# Power_Distro_Board_V3.net
KiCad netlist of a schematic drawn in EAGLE
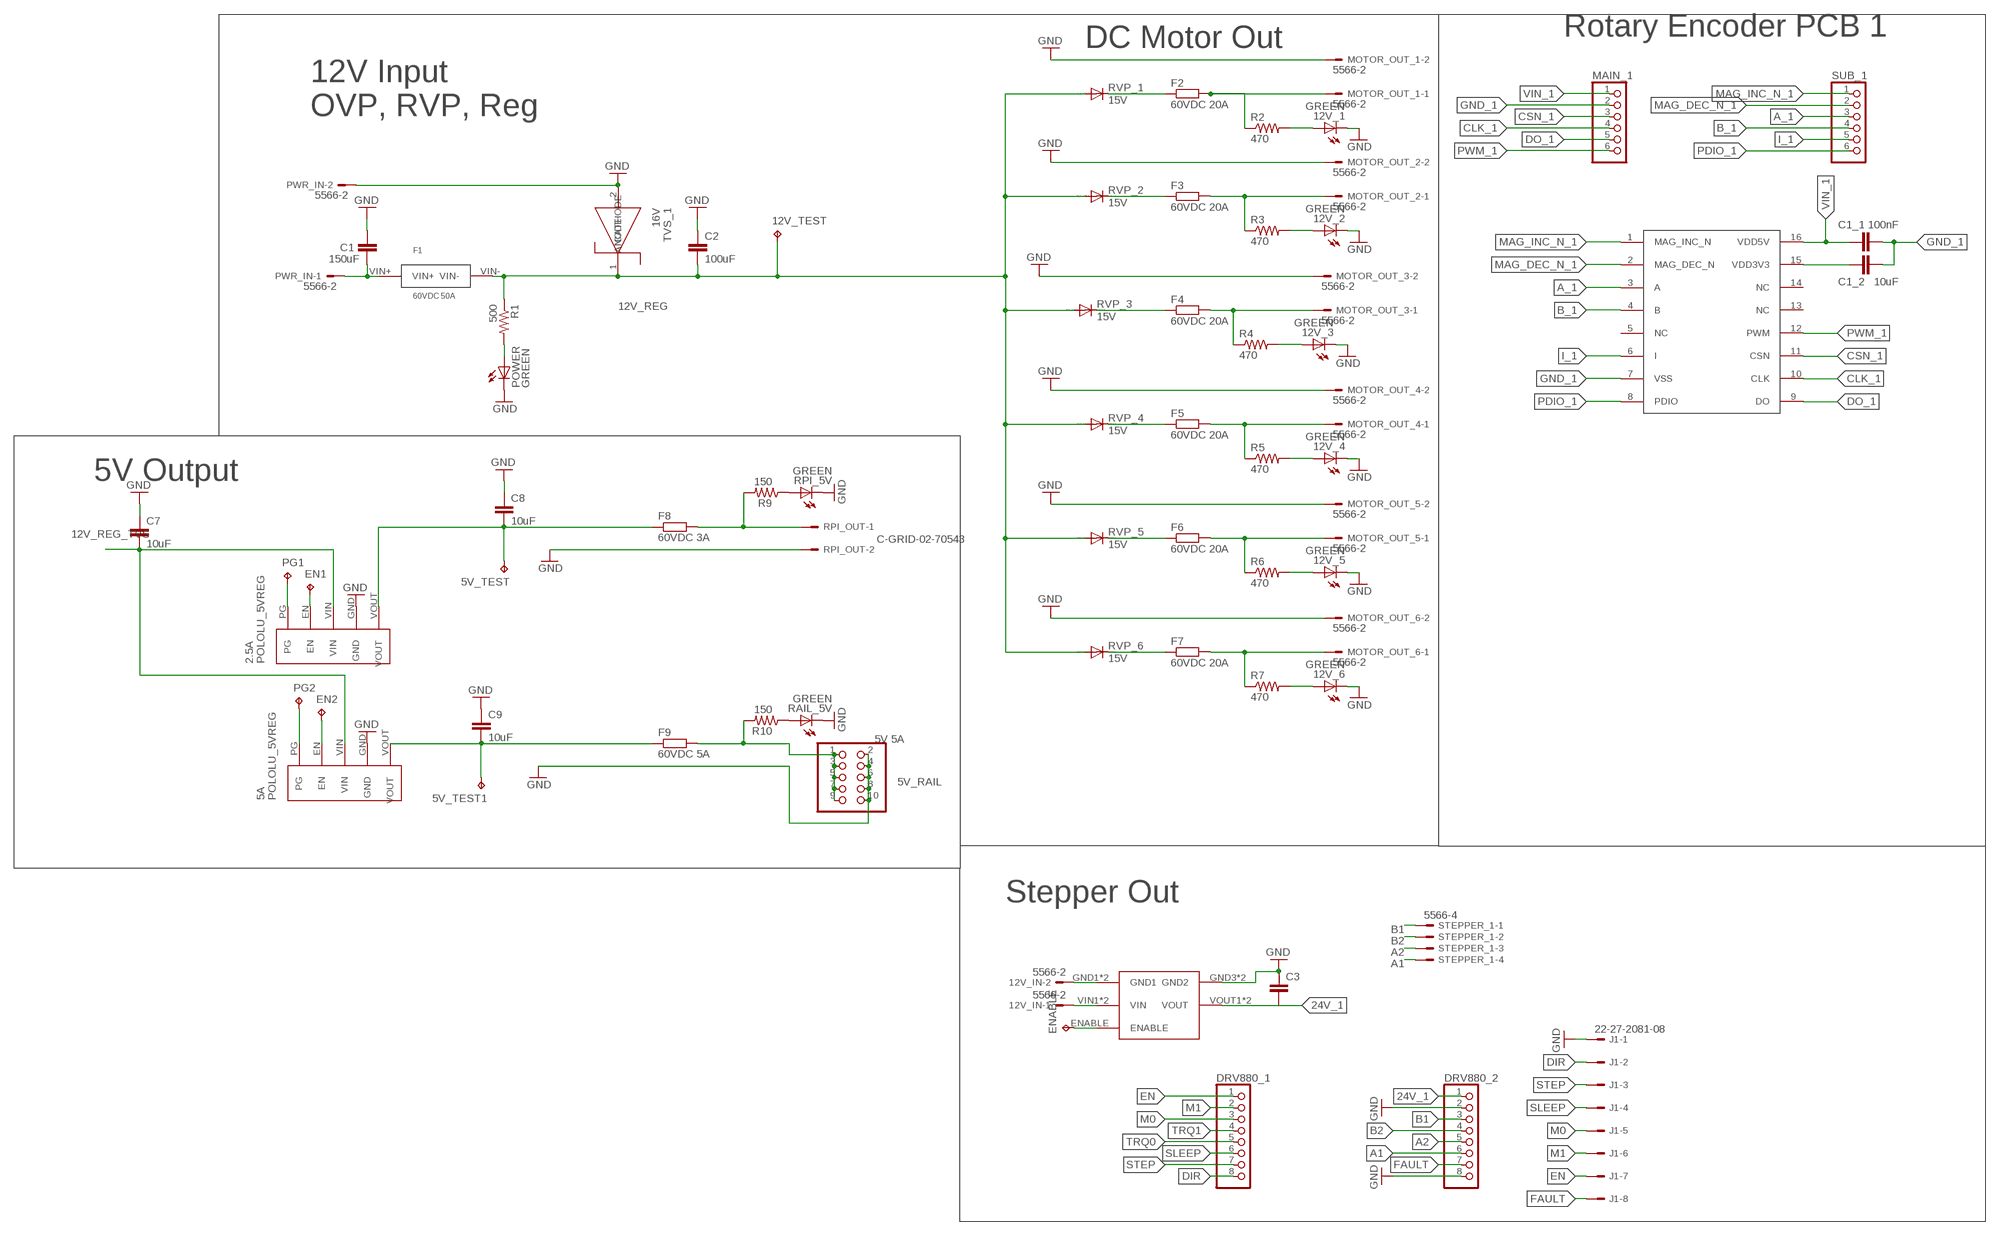
[diagram p0: schematic, sheet 1]

(export (version "E")
  (design (tool "Eeschema 10.0.6"))
  (components
    (comp (ref "2.5A")
      (value "POLOLU_5VREG")
      (footprint "eagle-import:SIP5")
      (libsource (lib "eagle-import") (part "POLOLU_5VREG"))
    )
    (comp (ref "5A")
      (value "POLOLU_5VREG")
      (footprint "eagle-import:SIP5")
      (libsource (lib "eagle-import") (part "POLOLU_5VREG"))
    )
    (comp (ref "5V_RAIL")
      (value "5V 5A")
      (footprint "eagle-import:2X05")
      (libsource (lib "eagle-import") (part "PINHD-2X5"))
    )
    (comp (ref "5V_TEST")
      (value "TPPAD1-13")
      (footprint "eagle-import:P1-13")
      (libsource (lib "eagle-import") (part "TPPAD1-13"))
    )
    (comp (ref "5V_TEST1")
      (value "TPPAD1-13")
      (footprint "eagle-import:P1-13")
      (libsource (lib "eagle-import") (part "TPPAD1-13"))
    )
    (comp (ref "12V_1")
      (value "GREEN")
      (footprint "eagle-import:SML1206")
      (libsource (lib "eagle-import") (part "LEDSML1206"))
    )
    (comp (ref "12V_2")
      (value "GREEN")
      (footprint "eagle-import:SML1206")
      (libsource (lib "eagle-import") (part "LEDSML1206"))
    )
    (comp (ref "12V_3")
      (value "GREEN")
      (footprint "eagle-import:SML1206")
      (libsource (lib "eagle-import") (part "LEDSML1206"))
    )
    (comp (ref "12V_4")
      (value "GREEN")
      (footprint "eagle-import:SML1206")
      (libsource (lib "eagle-import") (part "LEDSML1206"))
    )
    (comp (ref "12V_5")
      (value "GREEN")
      (footprint "eagle-import:SML1206")
      (libsource (lib "eagle-import") (part "LEDSML1206"))
    )
    (comp (ref "12V_6")
      (value "GREEN")
      (footprint "eagle-import:SML1206")
      (libsource (lib "eagle-import") (part "LEDSML1206"))
    )
    (comp (ref "12V_IN")
      (value "5566-2")
      (footprint "eagle-import:5566-2")
      (libsource (lib "eagle-import") (part "5566-2"))
    )
    (comp (ref "12V_TEST")
      (value "TPPAD1-13")
      (footprint "eagle-import:P1-13")
      (libsource (lib "eagle-import") (part "TPPAD1-13"))
    )
    (comp (ref "C1")
      (value "150uF")
      (footprint "eagle-import:C1206")
      (libsource (lib "eagle-import") (part "C-EUC1206"))
    )
    (comp (ref "C1_1")
      (value "100nF")
      (footprint "eagle-import:C1206")
      (libsource (lib "eagle-import") (part "C-EUC1206"))
    )
    (comp (ref "C1_2")
      (value "10uF")
      (footprint "eagle-import:C1206")
      (libsource (lib "eagle-import") (part "C-EUC1206"))
    )
    (comp (ref "C2")
      (value "100uF")
      (footprint "eagle-import:C1206")
      (libsource (lib "eagle-import") (part "C-EUC1206"))
    )
    (comp (ref "C3")
      (value "C-EUC1206")
      (footprint "eagle-import:C1206")
      (libsource (lib "eagle-import") (part "C-EUC1206"))
    )
    (comp (ref "C7")
      (value "10uF")
      (footprint "eagle-import:C1206")
      (libsource (lib "eagle-import") (part "C-EUC1206"))
    )
    (comp (ref "C8")
      (value "10uF")
      (footprint "eagle-import:C1206")
      (libsource (lib "eagle-import") (part "C-EUC1206"))
    )
    (comp (ref "C9")
      (value "10uF")
      (footprint "eagle-import:C1206")
      (libsource (lib "eagle-import") (part "C-EUC1206"))
    )
    (comp (ref "DRV880_1")
      (value "PINHD-1X8")
      (footprint "eagle-import:1X08")
      (libsource (lib "eagle-import") (part "PINHD-1X8"))
    )
    (comp (ref "DRV880_2")
      (value "PINHD-1X8")
      (footprint "eagle-import:1X08")
      (libsource (lib "eagle-import") (part "PINHD-1X8"))
    )
    (comp (ref "EN1")
      (value "TPPAD1-13")
      (footprint "eagle-import:P1-13")
      (libsource (lib "eagle-import") (part "TPPAD1-13"))
    )
    (comp (ref "EN2")
      (value "TPPAD1-13")
      (footprint "eagle-import:P1-13")
      (libsource (lib "eagle-import") (part "TPPAD1-13"))
    )
    (comp (ref "ENABLE")
      (value "TPPAD1-13")
      (footprint "eagle-import:P1-13")
      (libsource (lib "eagle-import") (part "TPPAD1-13"))
    )
    (comp (ref "ENC_1")
      (value "ENCODER_AS5045B")
      (footprint "eagle-import:SSOP16")
      (libsource (lib "eagle-import") (part "ENCODER_AS5045B"))
    )
    (comp (ref "F1")
      (value "60VDC 50A")
      (footprint "eagle-import:NANO")
      (libsource (lib "eagle-import") (part "LITTLEFUSENANO463"))
    )
    (comp (ref "F2")
      (value "60VDC 20A")
      (footprint "eagle-import:R1206W")
      (libsource (lib "eagle-import") (part "R-EU_R1206W"))
    )
    (comp (ref "F3")
      (value "60VDC 20A")
      (footprint "eagle-import:R1206W")
      (libsource (lib "eagle-import") (part "R-EU_R1206W"))
    )
    (comp (ref "F4")
      (value "60VDC 20A")
      (footprint "eagle-import:R1206W")
      (libsource (lib "eagle-import") (part "R-EU_R1206W"))
    )
    (comp (ref "F5")
      (value "60VDC 20A")
      (footprint "eagle-import:R1206W")
      (libsource (lib "eagle-import") (part "R-EU_R1206W"))
    )
    (comp (ref "F6")
      (value "60VDC 20A")
      (footprint "eagle-import:R1206W")
      (libsource (lib "eagle-import") (part "R-EU_R1206W"))
    )
    (comp (ref "F7")
      (value "60VDC 20A")
      (footprint "eagle-import:R1206W")
      (libsource (lib "eagle-import") (part "R-EU_R1206W"))
    )
    (comp (ref "F8")
      (value "60VDC 3A")
      (footprint "eagle-import:R1206W")
      (libsource (lib "eagle-import") (part "R-EU_R1206W"))
    )
    (comp (ref "F9")
      (value "60VDC 5A")
      (footprint "eagle-import:R1206W")
      (libsource (lib "eagle-import") (part "R-EU_R1206W"))
    )
    (comp (ref "J1")
      (value "22-27-2081-08")
      (footprint "eagle-import:6410-08")
      (libsource (lib "eagle-import") (part "22-?-0827-2081"))
    )
    (comp (ref "MAIN_1")
      (value "PINHD-1X6")
      (footprint "eagle-import:1X06")
      (libsource (lib "eagle-import") (part "PINHD-1X6"))
    )
    (comp (ref "MOTOR_OUT_1")
      (value "5566-2")
      (footprint "eagle-import:5566-2")
      (libsource (lib "eagle-import") (part "5566-2"))
    )
    (comp (ref "MOTOR_OUT_2")
      (value "5566-2")
      (footprint "eagle-import:5566-2")
      (libsource (lib "eagle-import") (part "5566-2"))
    )
    (comp (ref "MOTOR_OUT_3")
      (value "5566-2")
      (footprint "eagle-import:5566-2")
      (libsource (lib "eagle-import") (part "5566-2"))
    )
    (comp (ref "MOTOR_OUT_4")
      (value "5566-2")
      (footprint "eagle-import:5566-2")
      (libsource (lib "eagle-import") (part "5566-2"))
    )
    (comp (ref "MOTOR_OUT_5")
      (value "5566-2")
      (footprint "eagle-import:5566-2")
      (libsource (lib "eagle-import") (part "5566-2"))
    )
    (comp (ref "MOTOR_OUT_6")
      (value "5566-2")
      (footprint "eagle-import:5566-2")
      (libsource (lib "eagle-import") (part "5566-2"))
    )
    (comp (ref "PG1")
      (value "TPPAD1-13")
      (footprint "eagle-import:P1-13")
      (libsource (lib "eagle-import") (part "TPPAD1-13"))
    )
    (comp (ref "PG2")
      (value "TPPAD1-13")
      (footprint "eagle-import:P1-13")
      (libsource (lib "eagle-import") (part "TPPAD1-13"))
    )
    (comp (ref "POWER")
      (value "GREEN")
      (footprint "eagle-import:SML1206")
      (libsource (lib "eagle-import") (part "LEDSML1206"))
    )
    (comp (ref "PWR_IN")
      (value "5566-2")
      (footprint "eagle-import:5566-2")
      (libsource (lib "eagle-import") (part "5566-2"))
    )
    (comp (ref "R1")
      (value "500")
      (footprint "eagle-import:R1206")
      (libsource (lib "eagle-import") (part "R-US_R1206"))
    )
    (comp (ref "R2")
      (value "470")
      (footprint "eagle-import:R1206")
      (libsource (lib "eagle-import") (part "R-US_R1206"))
    )
    (comp (ref "R3")
      (value "470")
      (footprint "eagle-import:R1206")
      (libsource (lib "eagle-import") (part "R-US_R1206"))
    )
    (comp (ref "R4")
      (value "470")
      (footprint "eagle-import:R1206")
      (libsource (lib "eagle-import") (part "R-US_R1206"))
    )
    (comp (ref "R5")
      (value "470")
      (footprint "eagle-import:R1206")
      (libsource (lib "eagle-import") (part "R-US_R1206"))
    )
    (comp (ref "R6")
      (value "470")
      (footprint "eagle-import:R1206")
      (libsource (lib "eagle-import") (part "R-US_R1206"))
    )
    (comp (ref "R7")
      (value "470")
      (footprint "eagle-import:R1206")
      (libsource (lib "eagle-import") (part "R-US_R1206"))
    )
    (comp (ref "R9")
      (value "150")
      (footprint "eagle-import:R1206")
      (libsource (lib "eagle-import") (part "R-US_R1206"))
    )
    (comp (ref "R10")
      (value "150")
      (footprint "eagle-import:R1206")
      (libsource (lib "eagle-import") (part "R-US_R1206"))
    )
    (comp (ref "RAIL_5V")
      (value "GREEN")
      (footprint "eagle-import:SML1206")
      (libsource (lib "eagle-import") (part "LEDSML1206"))
    )
    (comp (ref "RPI_5V")
      (value "GREEN")
      (footprint "eagle-import:SML1206")
      (libsource (lib "eagle-import") (part "LEDSML1206"))
    )
    (comp (ref "RPI_OUT")
      (value "C-GRID-02-70543")
      (footprint "eagle-import:70543-02")
      (libsource (lib "eagle-import") (part "C-GRID-02-70543"))
    )
    (comp (ref "RVP_1")
      (value "15V")
      (footprint "eagle-import:TO220ACS")
      (libsource (lib "eagle-import") (part "BYT08P"))
    )
    (comp (ref "RVP_2")
      (value "15V")
      (footprint "eagle-import:TO220ACS")
      (libsource (lib "eagle-import") (part "BYT08P"))
    )
    (comp (ref "RVP_3")
      (value "15V")
      (footprint "eagle-import:TO220ACS")
      (libsource (lib "eagle-import") (part "BYT08P"))
    )
    (comp (ref "RVP_4")
      (value "15V")
      (footprint "eagle-import:TO220ACS")
      (libsource (lib "eagle-import") (part "BYT08P"))
    )
    (comp (ref "RVP_5")
      (value "15V")
      (footprint "eagle-import:TO220ACS")
      (libsource (lib "eagle-import") (part "BYT08P"))
    )
    (comp (ref "RVP_6")
      (value "15V")
      (footprint "eagle-import:TO220ACS")
      (libsource (lib "eagle-import") (part "BYT08P"))
    )
    (comp (ref "STEPPER_1")
      (value "5566-4")
      (footprint "eagle-import:5566-4")
      (libsource (lib "eagle-import") (part "5566-4"))
    )
    (comp (ref "SUB_1")
      (value "PINHD-1X6")
      (footprint "eagle-import:1X06")
      (libsource (lib "eagle-import") (part "PINHD-1X6"))
    )
    (comp (ref "TVS_1")
      (value "16V")
      (footprint "eagle-import:DO-214AC")
      (libsource (lib "eagle-import") (part "SMAJ26A_TVSSMA"))
    )
    (comp (ref "U$1")
      (value "POLOLU_24VSTEPUP")
      (footprint "eagle-import:2X4PIN_REG")
      (libsource (lib "eagle-import") (part "POLOLU_24VSTEPUP"))
    )
  )
  (nets
    (net (code "1") (name "/12V_REG") (class "Default")
      (node (ref "12V_TEST") (pin "TP") (pinfunction "TP_TP") (pintype "input"))
      (node (ref "C2") (pin "2") (pinfunction "2_2") (pintype "passive"))
      (node (ref "F1") (pin "VIN-") (pinfunction "VIN-_VIN-") (pintype "bidirectional"))
      (node (ref "R1") (pin "1") (pinfunction "1_1") (pintype "passive"))
      (node (ref "RVP_1") (pin "A") (pinfunction "A_A") (pintype "passive"))
      (node (ref "RVP_2") (pin "A") (pinfunction "A_A") (pintype "passive"))
      (node (ref "RVP_3") (pin "A") (pinfunction "A_A") (pintype "passive"))
      (node (ref "RVP_4") (pin "A") (pinfunction "A_A") (pintype "passive"))
      (node (ref "RVP_5") (pin "A") (pinfunction "A_A") (pintype "passive"))
      (node (ref "RVP_6") (pin "A") (pinfunction "A_A") (pintype "passive"))
      (node (ref "TVS_1") (pin "1") (pinfunction "CATHODE_1") (pintype "bidirectional"))
    )
    (net (code "2") (name "/12V_REG_TVS") (class "Default")
      (node (ref "2.5A") (pin "VIN") (pinfunction "VIN_VIN") (pintype "bidirectional"))
      (node (ref "5A") (pin "VIN") (pinfunction "VIN_VIN") (pintype "bidirectional"))
      (node (ref "C7") (pin "2") (pinfunction "2_2") (pintype "passive"))
    )
    (net (code "3") (name "24V_1") (class "Default")
      (node (ref "DRV880_2") (pin "1") (pinfunction "1_1") (pintype "passive"))
      (node (ref "U$1") (pin "VOUT1") (pinfunction "VOUT_VOUT1") (pintype "bidirectional"))
      (node (ref "U$1") (pin "VOUT2") (pinfunction "VOUT_VOUT2") (pintype "bidirectional"))
    )
    (net (code "4") (name "A1") (class "Default")
      (node (ref "DRV880_2") (pin "6") (pinfunction "6_6") (pintype "passive"))
      (node (ref "STEPPER_1") (pin "4") (pinfunction "S_4") (pintype "passive"))
    )
    (net (code "5") (name "A2") (class "Default")
      (node (ref "DRV880_2") (pin "5") (pinfunction "5_5") (pintype "passive"))
      (node (ref "STEPPER_1") (pin "3") (pinfunction "S_3") (pintype "passive"))
    )
    (net (code "6") (name "A_1") (class "Default")
      (node (ref "ENC_1") (pin "3") (pinfunction "A_3") (pintype "bidirectional"))
      (node (ref "SUB_1") (pin "3") (pinfunction "3_3") (pintype "passive"))
    )
    (net (code "7") (name "B1") (class "Default")
      (node (ref "DRV880_2") (pin "3") (pinfunction "3_3") (pintype "passive"))
      (node (ref "STEPPER_1") (pin "1") (pinfunction "S_1") (pintype "passive"))
    )
    (net (code "8") (name "B2") (class "Default")
      (node (ref "DRV880_2") (pin "4") (pinfunction "4_4") (pintype "passive"))
      (node (ref "STEPPER_1") (pin "2") (pinfunction "S_2") (pintype "passive"))
    )
    (net (code "9") (name "B_1") (class "Default")
      (node (ref "ENC_1") (pin "4") (pinfunction "B_4") (pintype "bidirectional"))
      (node (ref "SUB_1") (pin "4") (pinfunction "4_4") (pintype "passive"))
    )
    (net (code "10") (name "CLK_1") (class "Default")
      (node (ref "ENC_1") (pin "10") (pinfunction "CLK_10") (pintype "bidirectional"))
      (node (ref "MAIN_1") (pin "4") (pinfunction "4_4") (pintype "passive"))
    )
    (net (code "11") (name "CSN_1") (class "Default")
      (node (ref "ENC_1") (pin "11") (pinfunction "CSN_11") (pintype "bidirectional"))
      (node (ref "MAIN_1") (pin "3") (pinfunction "3_3") (pintype "passive"))
    )
    (net (code "12") (name "DIR") (class "Default")
      (node (ref "DRV880_1") (pin "8") (pinfunction "8_8") (pintype "passive"))
      (node (ref "J1") (pin "2") (pinfunction "S_2") (pintype "passive"))
    )
    (net (code "13") (name "DO_1") (class "Default")
      (node (ref "ENC_1") (pin "9") (pinfunction "DO_9") (pintype "bidirectional"))
      (node (ref "MAIN_1") (pin "5") (pinfunction "5_5") (pintype "passive"))
    )
    (net (code "14") (name "EN") (class "Default")
      (node (ref "DRV880_1") (pin "1") (pinfunction "1_1") (pintype "passive"))
      (node (ref "J1") (pin "7") (pinfunction "S_7") (pintype "passive"))
    )
    (net (code "15") (name "FAULT") (class "Default")
      (node (ref "DRV880_2") (pin "7") (pinfunction "7_7") (pintype "passive"))
      (node (ref "J1") (pin "8") (pinfunction "S_8") (pintype "passive"))
    )
    (net (code "16") (name "GND") (class "Default")
      (node (ref "12V_1") (pin "C") (pinfunction "C_C") (pintype "passive"))
      (node (ref "12V_2") (pin "C") (pinfunction "C_C") (pintype "passive"))
      (node (ref "12V_3") (pin "C") (pinfunction "C_C") (pintype "passive"))
      (node (ref "12V_4") (pin "C") (pinfunction "C_C") (pintype "passive"))
      (node (ref "12V_5") (pin "C") (pinfunction "C_C") (pintype "passive"))
      (node (ref "12V_6") (pin "C") (pinfunction "C_C") (pintype "passive"))
      (node (ref "2.5A") (pin "GND") (pinfunction "GND_GND") (pintype "bidirectional"))
      (node (ref "5A") (pin "GND") (pinfunction "GND_GND") (pintype "bidirectional"))
      (node (ref "5V_RAIL") (pin "10") (pinfunction "10_10") (pintype "passive"))
      (node (ref "5V_RAIL") (pin "2") (pinfunction "2_2") (pintype "passive"))
      (node (ref "5V_RAIL") (pin "4") (pinfunction "4_4") (pintype "passive"))
      (node (ref "5V_RAIL") (pin "6") (pinfunction "6_6") (pintype "passive"))
      (node (ref "5V_RAIL") (pin "8") (pinfunction "8_8") (pintype "passive"))
      (node (ref "C1") (pin "1") (pinfunction "1_1") (pintype "passive"))
      (node (ref "C2") (pin "1") (pinfunction "1_1") (pintype "passive"))
      (node (ref "C3") (pin "1") (pinfunction "1_1") (pintype "passive"))
      (node (ref "C7") (pin "1") (pinfunction "1_1") (pintype "passive"))
      (node (ref "C8") (pin "1") (pinfunction "1_1") (pintype "passive"))
      (node (ref "C9") (pin "1") (pinfunction "1_1") (pintype "passive"))
      (node (ref "DRV880_2") (pin "2") (pinfunction "2_2") (pintype "passive"))
      (node (ref "DRV880_2") (pin "8") (pinfunction "8_8") (pintype "passive"))
      (node (ref "J1") (pin "1") (pinfunction "S_1") (pintype "passive"))
      (node (ref "MOTOR_OUT_1") (pin "2") (pinfunction "S_2") (pintype "passive"))
      (node (ref "MOTOR_OUT_2") (pin "2") (pinfunction "S_2") (pintype "passive"))
      (node (ref "MOTOR_OUT_3") (pin "2") (pinfunction "S_2") (pintype "passive"))
      (node (ref "MOTOR_OUT_4") (pin "2") (pinfunction "S_2") (pintype "passive"))
      (node (ref "MOTOR_OUT_5") (pin "2") (pinfunction "S_2") (pintype "passive"))
      (node (ref "MOTOR_OUT_6") (pin "2") (pinfunction "S_2") (pintype "passive"))
      (node (ref "POWER") (pin "C") (pinfunction "C_C") (pintype "passive"))
      (node (ref "PWR_IN") (pin "2") (pinfunction "S_2") (pintype "passive"))
      (node (ref "RAIL_5V") (pin "C") (pinfunction "C_C") (pintype "passive"))
      (node (ref "RPI_5V") (pin "C") (pinfunction "C_C") (pintype "passive"))
      (node (ref "RPI_OUT") (pin "2") (pinfunction "S_2") (pintype "passive"))
      (node (ref "TVS_1") (pin "2") (pinfunction "ANODE_2") (pintype "bidirectional"))
      (node (ref "U$1") (pin "GND3") (pinfunction "GND2_GND3") (pintype "bidirectional"))
      (node (ref "U$1") (pin "GND4") (pinfunction "GND2_GND4") (pintype "bidirectional"))
    )
    (net (code "17") (name "GND_1") (class "Default")
      (node (ref "C1_1") (pin "2") (pinfunction "2_2") (pintype "passive"))
      (node (ref "C1_2") (pin "2") (pinfunction "2_2") (pintype "passive"))
      (node (ref "ENC_1") (pin "7") (pinfunction "VSS_7") (pintype "bidirectional"))
      (node (ref "MAIN_1") (pin "2") (pinfunction "2_2") (pintype "passive"))
    )
    (net (code "18") (name "I_1") (class "Default")
      (node (ref "ENC_1") (pin "6") (pinfunction "I_6") (pintype "bidirectional"))
      (node (ref "SUB_1") (pin "5") (pinfunction "5_5") (pintype "passive"))
    )
    (net (code "19") (name "M0") (class "Default")
      (node (ref "DRV880_1") (pin "3") (pinfunction "3_3") (pintype "passive"))
      (node (ref "J1") (pin "5") (pinfunction "S_5") (pintype "passive"))
    )
    (net (code "20") (name "M1") (class "Default")
      (node (ref "DRV880_1") (pin "2") (pinfunction "2_2") (pintype "passive"))
      (node (ref "J1") (pin "6") (pinfunction "S_6") (pintype "passive"))
    )
    (net (code "21") (name "MAG_DEC_N_1") (class "Default")
      (node (ref "ENC_1") (pin "2") (pinfunction "MAG_DEC_N_2") (pintype "bidirectional"))
      (node (ref "SUB_1") (pin "2") (pinfunction "2_2") (pintype "passive"))
    )
    (net (code "22") (name "MAG_INC_N_1") (class "Default")
      (node (ref "ENC_1") (pin "1") (pinfunction "MAG_INC_N_1") (pintype "bidirectional"))
      (node (ref "SUB_1") (pin "1") (pinfunction "1_1") (pintype "passive"))
    )
    (net (code "23") (name "Net-(2.5A-PadEN)") (class "Default")
      (node (ref "2.5A") (pin "EN") (pinfunction "EN_EN") (pintype "bidirectional"))
      (node (ref "EN1") (pin "TP") (pinfunction "TP_TP") (pintype "input"))
    )
    (net (code "24") (name "Net-(2.5A-PadPG)") (class "Default")
      (node (ref "2.5A") (pin "PG") (pinfunction "PG_PG") (pintype "bidirectional"))
      (node (ref "PG1") (pin "TP") (pinfunction "TP_TP") (pintype "input"))
    )
    (net (code "25") (name "Net-(2.5A-PadVOUT)") (class "Default")
      (node (ref "2.5A") (pin "VOUT") (pinfunction "VOUT_VOUT") (pintype "bidirectional"))
      (node (ref "5V_TEST") (pin "TP") (pinfunction "TP_TP") (pintype "input"))
      (node (ref "C8") (pin "2") (pinfunction "2_2") (pintype "passive"))
      (node (ref "F8") (pin "1") (pinfunction "1_1") (pintype "passive"))
    )
    (net (code "26") (name "Net-(5A-PadEN)") (class "Default")
      (node (ref "5A") (pin "EN") (pinfunction "EN_EN") (pintype "bidirectional"))
      (node (ref "EN2") (pin "TP") (pinfunction "TP_TP") (pintype "input"))
    )
    (net (code "27") (name "Net-(5A-PadPG)") (class "Default")
      (node (ref "5A") (pin "PG") (pinfunction "PG_PG") (pintype "bidirectional"))
      (node (ref "PG2") (pin "TP") (pinfunction "TP_TP") (pintype "input"))
    )
    (net (code "28") (name "Net-(5A-PadVOUT)") (class "Default")
      (node (ref "5A") (pin "VOUT") (pinfunction "VOUT_VOUT") (pintype "bidirectional"))
      (node (ref "5V_TEST1") (pin "TP") (pinfunction "TP_TP") (pintype "input"))
      (node (ref "C9") (pin "2") (pinfunction "2_2") (pintype "passive"))
      (node (ref "F9") (pin "1") (pinfunction "1_1") (pintype "passive"))
    )
    (net (code "29") (name "Net-(5V_RAIL-Pad1)") (class "Default")
      (node (ref "5V_RAIL") (pin "1") (pinfunction "1_1") (pintype "passive"))
      (node (ref "5V_RAIL") (pin "3") (pinfunction "3_3") (pintype "passive"))
      (node (ref "5V_RAIL") (pin "5") (pinfunction "5_5") (pintype "passive"))
      (node (ref "5V_RAIL") (pin "7") (pinfunction "7_7") (pintype "passive"))
      (node (ref "5V_RAIL") (pin "9") (pinfunction "9_9") (pintype "passive"))
      (node (ref "F9") (pin "2") (pinfunction "2_2") (pintype "passive"))
      (node (ref "R10") (pin "2") (pinfunction "2_2") (pintype "passive"))
    )
    (net (code "30") (name "Net-(12V_1-PadA)") (class "Default")
      (node (ref "12V_1") (pin "A") (pinfunction "A_A") (pintype "passive"))
      (node (ref "R2") (pin "2") (pinfunction "2_2") (pintype "passive"))
    )
    (net (code "31") (name "Net-(12V_2-PadA)") (class "Default")
      (node (ref "12V_2") (pin "A") (pinfunction "A_A") (pintype "passive"))
      (node (ref "R3") (pin "2") (pinfunction "2_2") (pintype "passive"))
    )
    (net (code "32") (name "Net-(12V_3-PadA)") (class "Default")
      (node (ref "12V_3") (pin "A") (pinfunction "A_A") (pintype "passive"))
      (node (ref "R4") (pin "2") (pinfunction "2_2") (pintype "passive"))
    )
    (net (code "33") (name "Net-(12V_4-PadA)") (class "Default")
      (node (ref "12V_4") (pin "A") (pinfunction "A_A") (pintype "passive"))
      (node (ref "R5") (pin "2") (pinfunction "2_2") (pintype "passive"))
    )
    (net (code "34") (name "Net-(12V_5-PadA)") (class "Default")
      (node (ref "12V_5") (pin "A") (pinfunction "A_A") (pintype "passive"))
      (node (ref "R6") (pin "2") (pinfunction "2_2") (pintype "passive"))
    )
    (net (code "35") (name "Net-(12V_6-PadA)") (class "Default")
      (node (ref "12V_6") (pin "A") (pinfunction "A_A") (pintype "passive"))
      (node (ref "R7") (pin "2") (pinfunction "2_2") (pintype "passive"))
    )
    (net (code "36") (name "Net-(12V_INA-S)") (class "Default")
      (node (ref "12V_IN") (pin "1") (pinfunction "S_1") (pintype "passive"))
      (node (ref "U$1") (pin "VIN1") (pinfunction "VIN_VIN1") (pintype "bidirectional"))
      (node (ref "U$1") (pin "VIN2") (pinfunction "VIN_VIN2") (pintype "bidirectional"))
    )
    (net (code "37") (name "Net-(12V_INB-S)") (class "Default")
      (node (ref "12V_IN") (pin "2") (pinfunction "S_2") (pintype "passive"))
      (node (ref "U$1") (pin "GND1") (pinfunction "GND1_GND1") (pintype "bidirectional"))
      (node (ref "U$1") (pin "GND2") (pinfunction "GND1_GND2") (pintype "bidirectional"))
    )
    (net (code "38") (name "Net-(ENABLE-PadTP)") (class "Default")
      (node (ref "ENABLE") (pin "TP") (pinfunction "TP_TP") (pintype "input"))
      (node (ref "U$1") (pin "ENABLE") (pinfunction "ENABLE_ENABLE") (pintype "bidirectional"))
    )
    (net (code "39") (name "Net-(ENC_1-VDD3V3)") (class "Default")
      (node (ref "C1_2") (pin "1") (pinfunction "1_1") (pintype "passive"))
      (node (ref "ENC_1") (pin "15") (pinfunction "VDD3V3_15") (pintype "bidirectional"))
    )
    (net (code "40") (name "Net-(F2-Pad1)") (class "Default")
      (node (ref "F2") (pin "1") (pinfunction "1_1") (pintype "passive"))
      (node (ref "RVP_1") (pin "C") (pinfunction "C_C") (pintype "passive"))
    )
    (net (code "41") (name "Net-(F3-Pad1)") (class "Default")
      (node (ref "F3") (pin "1") (pinfunction "1_1") (pintype "passive"))
      (node (ref "RVP_2") (pin "C") (pinfunction "C_C") (pintype "passive"))
    )
    (net (code "42") (name "Net-(F4-Pad1)") (class "Default")
      (node (ref "F4") (pin "1") (pinfunction "1_1") (pintype "passive"))
      (node (ref "RVP_3") (pin "C") (pinfunction "C_C") (pintype "passive"))
    )
    (net (code "43") (name "Net-(F5-Pad1)") (class "Default")
      (node (ref "F5") (pin "1") (pinfunction "1_1") (pintype "passive"))
      (node (ref "RVP_4") (pin "C") (pinfunction "C_C") (pintype "passive"))
    )
    (net (code "44") (name "Net-(F6-Pad1)") (class "Default")
      (node (ref "F6") (pin "1") (pinfunction "1_1") (pintype "passive"))
      (node (ref "RVP_5") (pin "C") (pinfunction "C_C") (pintype "passive"))
    )
    (net (code "45") (name "Net-(F7-Pad1)") (class "Default")
      (node (ref "F7") (pin "1") (pinfunction "1_1") (pintype "passive"))
      (node (ref "RVP_6") (pin "C") (pinfunction "C_C") (pintype "passive"))
    )
    (net (code "46") (name "Net-(MOTOR_OUT_1A-S)") (class "Default")
      (node (ref "F2") (pin "2") (pinfunction "2_2") (pintype "passive"))
      (node (ref "MOTOR_OUT_1") (pin "1") (pinfunction "S_1") (pintype "passive"))
      (node (ref "R2") (pin "1") (pinfunction "1_1") (pintype "passive"))
    )
    (net (code "47") (name "Net-(MOTOR_OUT_2A-S)") (class "Default")
      (node (ref "F3") (pin "2") (pinfunction "2_2") (pintype "passive"))
      (node (ref "MOTOR_OUT_2") (pin "1") (pinfunction "S_1") (pintype "passive"))
      (node (ref "R3") (pin "1") (pinfunction "1_1") (pintype "passive"))
    )
    (net (code "48") (name "Net-(MOTOR_OUT_3A-S)") (class "Default")
      (node (ref "F4") (pin "2") (pinfunction "2_2") (pintype "passive"))
      (node (ref "MOTOR_OUT_3") (pin "1") (pinfunction "S_1") (pintype "passive"))
      (node (ref "R4") (pin "1") (pinfunction "1_1") (pintype "passive"))
    )
    (net (code "49") (name "Net-(MOTOR_OUT_4A-S)") (class "Default")
      (node (ref "F5") (pin "2") (pinfunction "2_2") (pintype "passive"))
      (node (ref "MOTOR_OUT_4") (pin "1") (pinfunction "S_1") (pintype "passive"))
      (node (ref "R5") (pin "1") (pinfunction "1_1") (pintype "passive"))
    )
    (net (code "50") (name "Net-(MOTOR_OUT_5A-S)") (class "Default")
      (node (ref "F6") (pin "2") (pinfunction "2_2") (pintype "passive"))
      (node (ref "MOTOR_OUT_5") (pin "1") (pinfunction "S_1") (pintype "passive"))
      (node (ref "R6") (pin "1") (pinfunction "1_1") (pintype "passive"))
    )
    (net (code "51") (name "Net-(MOTOR_OUT_6A-S)") (class "Default")
      (node (ref "F7") (pin "2") (pinfunction "2_2") (pintype "passive"))
      (node (ref "MOTOR_OUT_6") (pin "1") (pinfunction "S_1") (pintype "passive"))
      (node (ref "R7") (pin "1") (pinfunction "1_1") (pintype "passive"))
    )
    (net (code "52") (name "Net-(POWER-PadA)") (class "Default")
      (node (ref "POWER") (pin "A") (pinfunction "A_A") (pintype "passive"))
      (node (ref "R1") (pin "2") (pinfunction "2_2") (pintype "passive"))
    )
    (net (code "53") (name "Net-(PWR_INA-S)") (class "Default")
      (node (ref "C1") (pin "2") (pinfunction "2_2") (pintype "passive"))
      (node (ref "F1") (pin "VIN+") (pinfunction "VIN+_VIN+") (pintype "bidirectional"))
      (node (ref "PWR_IN") (pin "1") (pinfunction "S_1") (pintype "passive"))
    )
    (net (code "54") (name "Net-(R9-Pad1)") (class "Default")
      (node (ref "R9") (pin "1") (pinfunction "1_1") (pintype "passive"))
      (node (ref "RPI_5V") (pin "A") (pinfunction "A_A") (pintype "passive"))
    )
    (net (code "55") (name "Net-(R10-Pad1)") (class "Default")
      (node (ref "R10") (pin "1") (pinfunction "1_1") (pintype "passive"))
      (node (ref "RAIL_5V") (pin "A") (pinfunction "A_A") (pintype "passive"))
    )
    (net (code "56") (name "Net-(RPI_OUTA-S)") (class "Default")
      (node (ref "F8") (pin "2") (pinfunction "2_2") (pintype "passive"))
      (node (ref "R9") (pin "2") (pinfunction "2_2") (pintype "passive"))
      (node (ref "RPI_OUT") (pin "1") (pinfunction "S_1") (pintype "passive"))
    )
    (net (code "57") (name "PDIO_1") (class "Default")
      (node (ref "ENC_1") (pin "8") (pinfunction "PDIO_8") (pintype "bidirectional"))
      (node (ref "SUB_1") (pin "6") (pinfunction "6_6") (pintype "passive"))
    )
    (net (code "58") (name "PWM_1") (class "Default")
      (node (ref "ENC_1") (pin "12") (pinfunction "PWM_12") (pintype "bidirectional"))
      (node (ref "MAIN_1") (pin "6") (pinfunction "6_6") (pintype "passive"))
    )
    (net (code "59") (name "SLEEP") (class "Default")
      (node (ref "DRV880_1") (pin "6") (pinfunction "6_6") (pintype "passive"))
      (node (ref "J1") (pin "4") (pinfunction "S_4") (pintype "passive"))
    )
    (net (code "60") (name "STEP") (class "Default")
      (node (ref "DRV880_1") (pin "7") (pinfunction "7_7") (pintype "passive"))
      (node (ref "J1") (pin "3") (pinfunction "S_3") (pintype "passive"))
    )
    (net (code "61") (name "TRQ0") (class "Default")
      (node (ref "DRV880_1") (pin "5") (pinfunction "5_5") (pintype "passive"))
    )
    (net (code "62") (name "TRQ1") (class "Default")
      (node (ref "DRV880_1") (pin "4") (pinfunction "4_4") (pintype "passive"))
    )
    (net (code "63") (name "VIN_1") (class "Default")
      (node (ref "C1_1") (pin "1") (pinfunction "1_1") (pintype "passive"))
      (node (ref "ENC_1") (pin "16") (pinfunction "VDD5V_16") (pintype "bidirectional"))
      (node (ref "MAIN_1") (pin "1") (pinfunction "1_1") (pintype "passive"))
    )
    (net (code "64") (name "unconnected-(C3-Pad2)") (class "Default")
      (node (ref "C3") (pin "2") (pinfunction "2_2") (pintype "passive"))
    )
    (net (code "65") (name "unconnected-(ENC_1-NC-Pad5)") (class "Default")
      (node (ref "ENC_1") (pin "5") (pinfunction "NC_5") (pintype "bidirectional"))
    )
    (net (code "66") (name "unconnected-(ENC_1-NC-Pad13)") (class "Default")
      (node (ref "ENC_1") (pin "13") (pinfunction "NC_13") (pintype "bidirectional"))
    )
    (net (code "67") (name "unconnected-(ENC_1-NC-Pad14)") (class "Default")
      (node (ref "ENC_1") (pin "14") (pinfunction "NC_14") (pintype "bidirectional"))
    )
  )
)
